# PCB-VU-SE-1.net
KiCad netlist of a schematic drawn in EAGLE
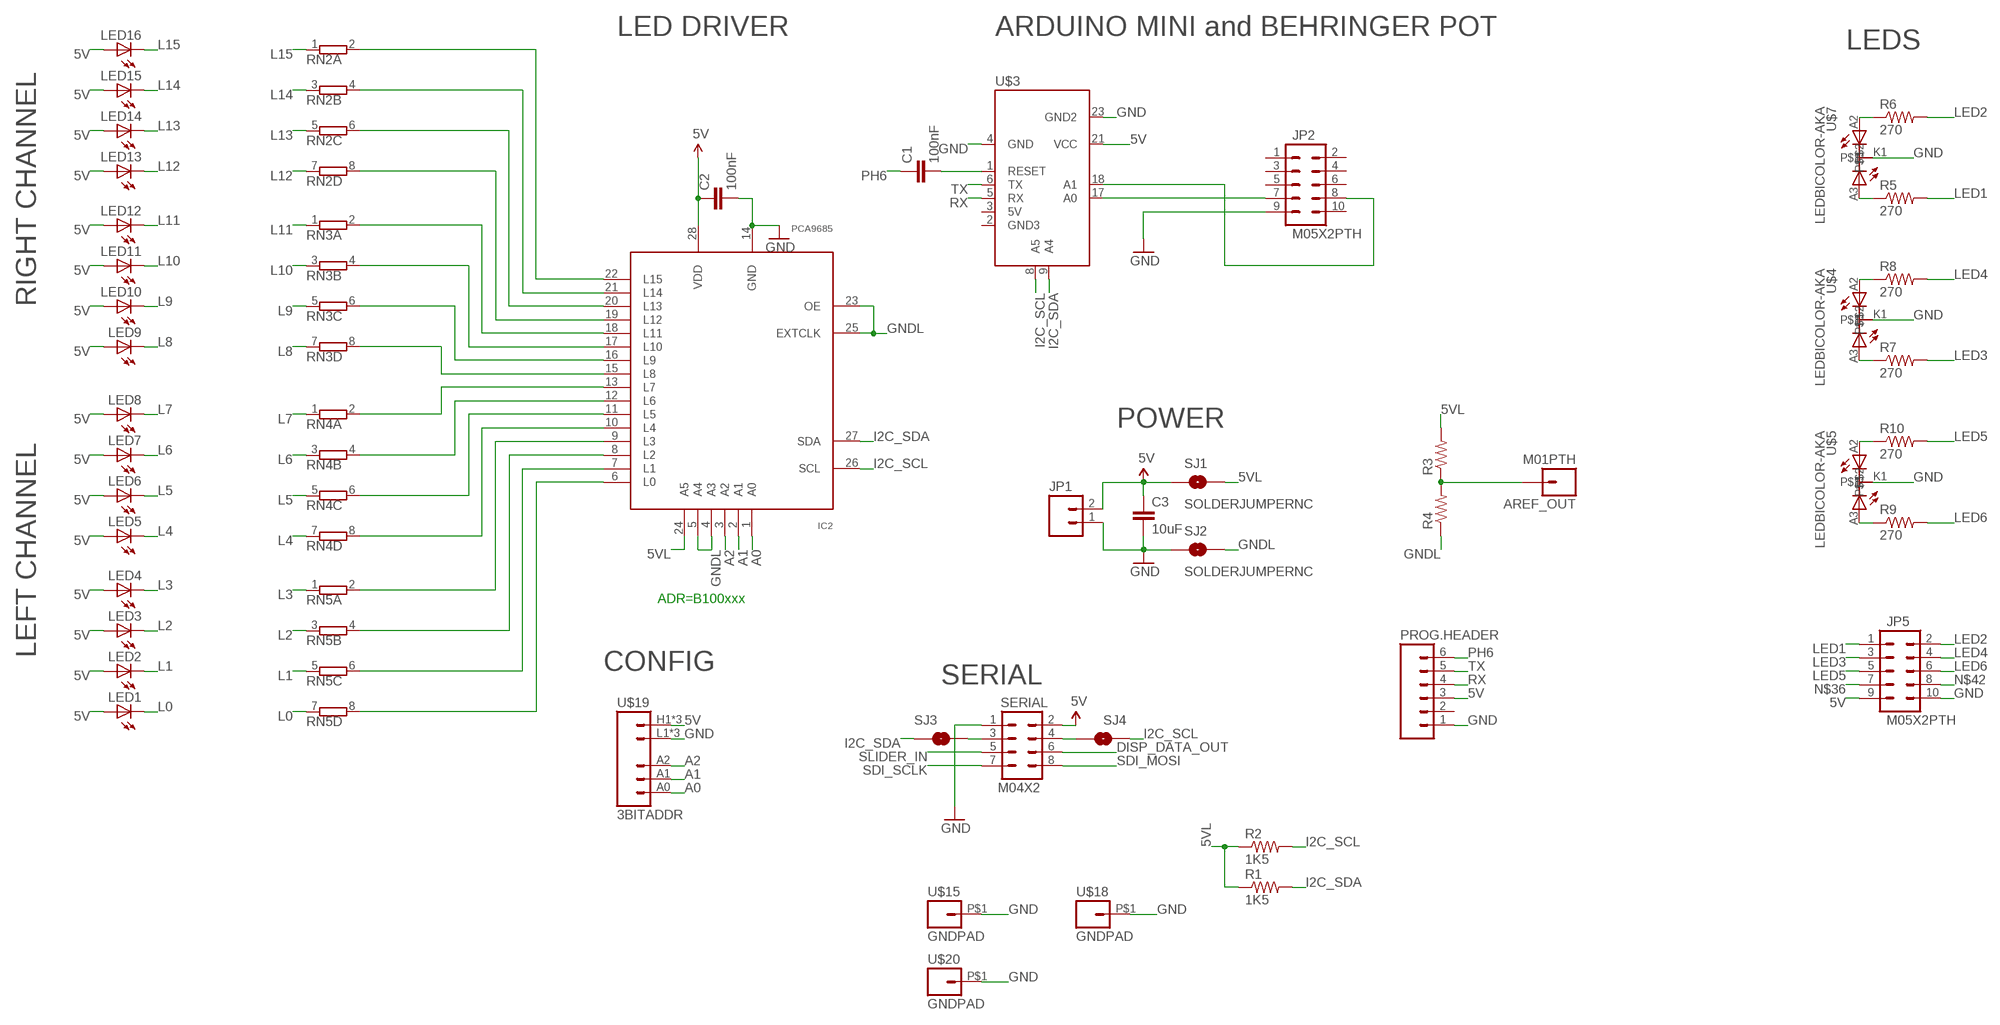
[diagram p0: schematic, sheet 1]

(export (version "E")
  (design (tool "Eeschema 10.0.6"))
  (components
    (comp (ref "AREF_OUT")
      (value "M01PTH")
      (footprint "eagle-import:1X01")
      (libsource (lib "eagle-import") (part "M01PTH"))
    )
    (comp (ref "C1")
      (value "100nF")
      (footprint "eagle-import:0603-CAP")
      (libsource (lib "eagle-import") (part "CAP0603-CAP"))
    )
    (comp (ref "C2")
      (value "100nF")
      (footprint "eagle-import:0603-CAP")
      (libsource (lib "eagle-import") (part "CAP0603-CAP"))
    )
    (comp (ref "C3")
      (value "10uF")
      (footprint "eagle-import:0805")
      (libsource (lib "eagle-import") (part "CAP0805"))
    )
    (comp (ref "IC2")
      (value "PCA9685")
      (footprint "eagle-import:TSSOP28")
      (libsource (lib "eagle-import") (part "PCA9685"))
    )
    (comp (ref "JP1")
      (value "M02PTH")
      (footprint "eagle-import:1X02")
      (libsource (lib "eagle-import") (part "M02PTH"))
    )
    (comp (ref "JP2")
      (value "M05X2PTH")
      (footprint "eagle-import:AVR_ICSP")
      (libsource (lib "eagle-import") (part "M05X2PTH"))
    )
    (comp (ref "JP5")
      (value "M05X2PTH")
      (footprint "eagle-import:AVR_ICSP")
      (libsource (lib "eagle-import") (part "M05X2PTH"))
    )
    (comp (ref "LED1")
      (value "LED3MM")
      (footprint "eagle-import:LED3MM")
      (libsource (lib "eagle-import") (part "LED3MM"))
    )
    (comp (ref "LED2")
      (value "LED3MM")
      (footprint "eagle-import:LED3MM")
      (libsource (lib "eagle-import") (part "LED3MM"))
    )
    (comp (ref "LED3")
      (value "LED3MM")
      (footprint "eagle-import:LED3MM")
      (libsource (lib "eagle-import") (part "LED3MM"))
    )
    (comp (ref "LED4")
      (value "LED3MM")
      (footprint "eagle-import:LED3MM")
      (libsource (lib "eagle-import") (part "LED3MM"))
    )
    (comp (ref "LED5")
      (value "LED3MM")
      (footprint "eagle-import:LED3MM")
      (libsource (lib "eagle-import") (part "LED3MM"))
    )
    (comp (ref "LED6")
      (value "LED3MM")
      (footprint "eagle-import:LED3MM")
      (libsource (lib "eagle-import") (part "LED3MM"))
    )
    (comp (ref "LED7")
      (value "LED3MM")
      (footprint "eagle-import:LED3MM")
      (libsource (lib "eagle-import") (part "LED3MM"))
    )
    (comp (ref "LED8")
      (value "LED3MM")
      (footprint "eagle-import:LED3MM")
      (libsource (lib "eagle-import") (part "LED3MM"))
    )
    (comp (ref "LED9")
      (value "LED3MM")
      (footprint "eagle-import:LED3MM")
      (libsource (lib "eagle-import") (part "LED3MM"))
    )
    (comp (ref "LED10")
      (value "LED3MM")
      (footprint "eagle-import:LED3MM")
      (libsource (lib "eagle-import") (part "LED3MM"))
    )
    (comp (ref "LED11")
      (value "LED3MM")
      (footprint "eagle-import:LED3MM")
      (libsource (lib "eagle-import") (part "LED3MM"))
    )
    (comp (ref "LED12")
      (value "LED3MM")
      (footprint "eagle-import:LED3MM")
      (libsource (lib "eagle-import") (part "LED3MM"))
    )
    (comp (ref "LED13")
      (value "LED3MM")
      (footprint "eagle-import:LED3MM")
      (libsource (lib "eagle-import") (part "LED3MM"))
    )
    (comp (ref "LED14")
      (value "LED3MM")
      (footprint "eagle-import:LED3MM")
      (libsource (lib "eagle-import") (part "LED3MM"))
    )
    (comp (ref "LED15")
      (value "LED3MM")
      (footprint "eagle-import:LED3MM")
      (libsource (lib "eagle-import") (part "LED3MM"))
    )
    (comp (ref "LED16")
      (value "LED3MM")
      (footprint "eagle-import:LED3MM")
      (libsource (lib "eagle-import") (part "LED3MM"))
    )
    (comp (ref "PROG.HEADER")
      (value "M06LOCK")
      (footprint "eagle-import:1X06_LOCK")
      (libsource (lib "eagle-import") (part "M06LOCK"))
    )
    (comp (ref "R1")
      (value "1K5")
      (footprint "eagle-import:0603-RES")
      (libsource (lib "eagle-import") (part "RESISTOR0603-RES"))
    )
    (comp (ref "R2")
      (value "1K5")
      (footprint "eagle-import:0603-RES")
      (libsource (lib "eagle-import") (part "RESISTOR0603-RES"))
    )
    (comp (ref "R3")
      (value "RESISTOR0603-RES")
      (footprint "eagle-import:0603-RES")
      (libsource (lib "eagle-import") (part "RESISTOR0603-RES"))
    )
    (comp (ref "R4")
      (value "RESISTOR0603-RES")
      (footprint "eagle-import:0603-RES")
      (libsource (lib "eagle-import") (part "RESISTOR0603-RES"))
    )
    (comp (ref "R5")
      (value "270")
      (footprint "eagle-import:0603-RES")
      (libsource (lib "eagle-import") (part "RESISTOR0603-RES"))
    )
    (comp (ref "R6")
      (value "270")
      (footprint "eagle-import:0603-RES")
      (libsource (lib "eagle-import") (part "RESISTOR0603-RES"))
    )
    (comp (ref "R7")
      (value "270")
      (footprint "eagle-import:0603-RES")
      (libsource (lib "eagle-import") (part "RESISTOR0603-RES"))
    )
    (comp (ref "R8")
      (value "270")
      (footprint "eagle-import:0603-RES")
      (libsource (lib "eagle-import") (part "RESISTOR0603-RES"))
    )
    (comp (ref "R9")
      (value "270")
      (footprint "eagle-import:0603-RES")
      (libsource (lib "eagle-import") (part "RESISTOR0603-RES"))
    )
    (comp (ref "R10")
      (value "270")
      (footprint "eagle-import:0603-RES")
      (libsource (lib "eagle-import") (part "RESISTOR0603-RES"))
    )
    (comp (ref "RN2")
      (value "E4R")
      (footprint "eagle-import:SIL8")
      (libsource (lib "eagle-import") (part "E4R"))
    )
    (comp (ref "RN3")
      (value "E4R")
      (footprint "eagle-import:SIL8")
      (libsource (lib "eagle-import") (part "E4R"))
    )
    (comp (ref "RN4")
      (value "E4R")
      (footprint "eagle-import:SIL8")
      (libsource (lib "eagle-import") (part "E4R"))
    )
    (comp (ref "RN5")
      (value "E4R")
      (footprint "eagle-import:SIL8")
      (libsource (lib "eagle-import") (part "E4R"))
    )
    (comp (ref "SERIAL")
      (value "M04X2")
      (footprint "eagle-import:2X4")
      (libsource (lib "eagle-import") (part "M04X2"))
    )
    (comp (ref "SJ1")
      (value "SOLDERJUMPERNC")
      (footprint "eagle-import:SJ_2S")
      (libsource (lib "eagle-import") (part "SOLDERJUMPERNC"))
    )
    (comp (ref "SJ2")
      (value "SOLDERJUMPERNC")
      (footprint "eagle-import:SJ_2S")
      (libsource (lib "eagle-import") (part "SOLDERJUMPERNC"))
    )
    (comp (ref "SJ3")
      (value "SOLDERJUMPERNC")
      (footprint "eagle-import:SJ_2S")
      (libsource (lib "eagle-import") (part "SOLDERJUMPERNC"))
    )
    (comp (ref "SJ4")
      (value "SOLDERJUMPERNC")
      (footprint "eagle-import:SJ_2S")
      (libsource (lib "eagle-import") (part "SOLDERJUMPERNC"))
    )
    (comp (ref "U$3")
      (value "ARDUINO_MINI_SE1")
      (footprint "eagle-import:ARDUINO_MINI_SE1")
      (libsource (lib "eagle-import") (part "ARDUINO_MINI_SE1"))
    )
    (comp (ref "U$4")
      (value "LEDBICOLOR-AKA")
      (footprint "eagle-import:LED5MM-BICOLOR")
      (libsource (lib "eagle-import") (part "LEDBICOLOR-AKA"))
    )
    (comp (ref "U$5")
      (value "LEDBICOLOR-AKA")
      (footprint "eagle-import:LED5MM-BICOLOR")
      (libsource (lib "eagle-import") (part "LEDBICOLOR-AKA"))
    )
    (comp (ref "U$7")
      (value "LEDBICOLOR-AKA")
      (footprint "eagle-import:LED5MM-BICOLOR")
      (libsource (lib "eagle-import") (part "LEDBICOLOR-AKA"))
    )
    (comp (ref "U$15")
      (value "GNDPAD")
      (footprint "eagle-import:3.2MMPAD")
      (libsource (lib "eagle-import") (part "GNDPAD"))
    )
    (comp (ref "U$18")
      (value "GNDPAD")
      (footprint "eagle-import:3.2MMPAD")
      (libsource (lib "eagle-import") (part "GNDPAD"))
    )
    (comp (ref "U$19")
      (value "3BITADDR")
      (footprint "eagle-import:3BITADDR")
      (libsource (lib "eagle-import") (part "3BITADDR"))
    )
    (comp (ref "U$20")
      (value "GNDPAD")
      (footprint "eagle-import:3.2MMPAD")
      (libsource (lib "eagle-import") (part "GNDPAD"))
    )
  )
  (nets
    (net (code "1") (name "/5VL") (class "Default")
      (node (ref "IC2") (pin "24") (pinfunction "A5_24") (pintype "input"))
      (node (ref "R1") (pin "1") (pinfunction "1_1") (pintype "passive"))
      (node (ref "R2") (pin "1") (pinfunction "1_1") (pintype "passive"))
      (node (ref "R3") (pin "2") (pinfunction "2_2") (pintype "passive"))
      (node (ref "SJ1") (pin "2") (pinfunction "2_2") (pintype "passive"))
    )
    (net (code "2") (name "/A0") (class "Default")
      (node (ref "IC2") (pin "1") (pinfunction "A0_1") (pintype "input"))
      (node (ref "U$19") (pin "A0") (pinfunction "A0_A0") (pintype "passive"))
    )
    (net (code "3") (name "/A1") (class "Default")
      (node (ref "IC2") (pin "2") (pinfunction "A1_2") (pintype "input"))
      (node (ref "U$19") (pin "A1") (pinfunction "A1_A1") (pintype "passive"))
    )
    (net (code "4") (name "/A2") (class "Default")
      (node (ref "IC2") (pin "3") (pinfunction "A2_3") (pintype "input"))
      (node (ref "U$19") (pin "A2") (pinfunction "A2_A2") (pintype "passive"))
    )
    (net (code "5") (name "/DISP_DATA_OUT") (class "Default")
      (node (ref "SERIAL") (pin "6") (pinfunction "6_6") (pintype "passive"))
    )
    (net (code "6") (name "/GNDL") (class "Default")
      (node (ref "IC2") (pin "23") (pinfunction "OE_23") (pintype "input"))
      (node (ref "IC2") (pin "25") (pinfunction "EXTCLK_25") (pintype "input"))
      (node (ref "IC2") (pin "4") (pinfunction "A3_4") (pintype "input"))
      (node (ref "IC2") (pin "5") (pinfunction "A4_5") (pintype "input"))
      (node (ref "R4") (pin "1") (pinfunction "1_1") (pintype "passive"))
      (node (ref "SJ2") (pin "2") (pinfunction "2_2") (pintype "passive"))
    )
    (net (code "7") (name "/I2C_SCL") (class "Default")
      (node (ref "IC2") (pin "26") (pinfunction "SCL_26") (pintype "input"))
      (node (ref "R2") (pin "2") (pinfunction "2_2") (pintype "passive"))
      (node (ref "SJ4") (pin "2") (pinfunction "2_2") (pintype "passive"))
      (node (ref "U$3") (pin "8") (pinfunction "A5_8") (pintype "bidirectional"))
    )
    (net (code "8") (name "/I2C_SDA") (class "Default")
      (node (ref "IC2") (pin "27") (pinfunction "SDA_27") (pintype "input"))
      (node (ref "R1") (pin "2") (pinfunction "2_2") (pintype "passive"))
      (node (ref "SJ3") (pin "1") (pinfunction "1_1") (pintype "passive"))
      (node (ref "U$3") (pin "9") (pinfunction "A4_9") (pintype "bidirectional"))
    )
    (net (code "9") (name "/L0") (class "Default")
      (node (ref "LED1") (pin "K") (pinfunction "C_K") (pintype "passive"))
      (node (ref "RN5") (pin "7") (pinfunction "1_7") (pintype "passive"))
    )
    (net (code "10") (name "/L1") (class "Default")
      (node (ref "LED2") (pin "K") (pinfunction "C_K") (pintype "passive"))
      (node (ref "RN5") (pin "5") (pinfunction "1_5") (pintype "passive"))
    )
    (net (code "11") (name "/L2") (class "Default")
      (node (ref "LED3") (pin "K") (pinfunction "C_K") (pintype "passive"))
      (node (ref "RN5") (pin "3") (pinfunction "1_3") (pintype "passive"))
    )
    (net (code "12") (name "/L3") (class "Default")
      (node (ref "LED4") (pin "K") (pinfunction "C_K") (pintype "passive"))
      (node (ref "RN5") (pin "1") (pinfunction "1_1") (pintype "passive"))
    )
    (net (code "13") (name "/L4") (class "Default")
      (node (ref "LED5") (pin "K") (pinfunction "C_K") (pintype "passive"))
      (node (ref "RN4") (pin "7") (pinfunction "1_7") (pintype "passive"))
    )
    (net (code "14") (name "/L5") (class "Default")
      (node (ref "LED6") (pin "K") (pinfunction "C_K") (pintype "passive"))
      (node (ref "RN4") (pin "5") (pinfunction "1_5") (pintype "passive"))
    )
    (net (code "15") (name "/L6") (class "Default")
      (node (ref "LED7") (pin "K") (pinfunction "C_K") (pintype "passive"))
      (node (ref "RN4") (pin "3") (pinfunction "1_3") (pintype "passive"))
    )
    (net (code "16") (name "/L7") (class "Default")
      (node (ref "LED8") (pin "K") (pinfunction "C_K") (pintype "passive"))
      (node (ref "RN4") (pin "1") (pinfunction "1_1") (pintype "passive"))
    )
    (net (code "17") (name "/L8") (class "Default")
      (node (ref "LED9") (pin "K") (pinfunction "C_K") (pintype "passive"))
      (node (ref "RN3") (pin "7") (pinfunction "1_7") (pintype "passive"))
    )
    (net (code "18") (name "/L9") (class "Default")
      (node (ref "LED10") (pin "K") (pinfunction "C_K") (pintype "passive"))
      (node (ref "RN3") (pin "5") (pinfunction "1_5") (pintype "passive"))
    )
    (net (code "19") (name "/L10") (class "Default")
      (node (ref "LED11") (pin "K") (pinfunction "C_K") (pintype "passive"))
      (node (ref "RN3") (pin "3") (pinfunction "1_3") (pintype "passive"))
    )
    (net (code "20") (name "/L11") (class "Default")
      (node (ref "LED12") (pin "K") (pinfunction "C_K") (pintype "passive"))
      (node (ref "RN3") (pin "1") (pinfunction "1_1") (pintype "passive"))
    )
    (net (code "21") (name "/L12") (class "Default")
      (node (ref "LED13") (pin "K") (pinfunction "C_K") (pintype "passive"))
      (node (ref "RN2") (pin "7") (pinfunction "1_7") (pintype "passive"))
    )
    (net (code "22") (name "/L13") (class "Default")
      (node (ref "LED14") (pin "K") (pinfunction "C_K") (pintype "passive"))
      (node (ref "RN2") (pin "5") (pinfunction "1_5") (pintype "passive"))
    )
    (net (code "23") (name "/L14") (class "Default")
      (node (ref "LED15") (pin "K") (pinfunction "C_K") (pintype "passive"))
      (node (ref "RN2") (pin "3") (pinfunction "1_3") (pintype "passive"))
    )
    (net (code "24") (name "/L15") (class "Default")
      (node (ref "LED16") (pin "K") (pinfunction "C_K") (pintype "passive"))
      (node (ref "RN2") (pin "1") (pinfunction "1_1") (pintype "passive"))
    )
    (net (code "25") (name "/LED1") (class "Default")
      (node (ref "JP5") (pin "1") (pinfunction "1_1") (pintype "passive"))
      (node (ref "R5") (pin "2") (pinfunction "2_2") (pintype "passive"))
    )
    (net (code "26") (name "/LED2") (class "Default")
      (node (ref "JP5") (pin "2") (pinfunction "2_2") (pintype "passive"))
      (node (ref "R6") (pin "2") (pinfunction "2_2") (pintype "passive"))
    )
    (net (code "27") (name "/LED3") (class "Default")
      (node (ref "JP5") (pin "3") (pinfunction "3_3") (pintype "passive"))
      (node (ref "R7") (pin "2") (pinfunction "2_2") (pintype "passive"))
    )
    (net (code "28") (name "/LED4") (class "Default")
      (node (ref "JP5") (pin "4") (pinfunction "4_4") (pintype "passive"))
      (node (ref "R8") (pin "2") (pinfunction "2_2") (pintype "passive"))
    )
    (net (code "29") (name "/LED5") (class "Default")
      (node (ref "JP5") (pin "5") (pinfunction "5_5") (pintype "passive"))
      (node (ref "R10") (pin "2") (pinfunction "2_2") (pintype "passive"))
    )
    (net (code "30") (name "/LED6") (class "Default")
      (node (ref "JP5") (pin "6") (pinfunction "6_6") (pintype "passive"))
      (node (ref "R9") (pin "2") (pinfunction "2_2") (pintype "passive"))
    )
    (net (code "31") (name "/N$36") (class "Default")
      (node (ref "JP5") (pin "7") (pinfunction "7_7") (pintype "passive"))
    )
    (net (code "32") (name "/N$42") (class "Default")
      (node (ref "JP5") (pin "8") (pinfunction "8_8") (pintype "passive"))
    )
    (net (code "33") (name "/PH6") (class "Default")
      (node (ref "C1") (pin "1") (pinfunction "1_1") (pintype "passive"))
      (node (ref "PROG.HEADER") (pin "6") (pinfunction "6_6") (pintype "passive"))
    )
    (net (code "34") (name "/RX") (class "Default")
      (node (ref "PROG.HEADER") (pin "4") (pinfunction "4_4") (pintype "passive"))
      (node (ref "U$3") (pin "5") (pinfunction "RX_5") (pintype "bidirectional"))
    )
    (net (code "35") (name "/SDI_MOSI") (class "Default")
      (node (ref "SERIAL") (pin "8") (pinfunction "8_8") (pintype "passive"))
    )
    (net (code "36") (name "/SDI_SCLK") (class "Default")
      (node (ref "SERIAL") (pin "7") (pinfunction "7_7") (pintype "passive"))
    )
    (net (code "37") (name "/SLIDER_IN") (class "Default")
      (node (ref "SERIAL") (pin "5") (pinfunction "5_5") (pintype "passive"))
    )
    (net (code "38") (name "/TX") (class "Default")
      (node (ref "PROG.HEADER") (pin "5") (pinfunction "5_5") (pintype "passive"))
      (node (ref "U$3") (pin "6") (pinfunction "TX_6") (pintype "bidirectional"))
    )
    (net (code "39") (name "5V") (class "Default")
      (node (ref "C2") (pin "1") (pinfunction "1_1") (pintype "passive"))
      (node (ref "C3") (pin "1") (pinfunction "1_1") (pintype "passive"))
      (node (ref "IC2") (pin "28") (pinfunction "VDD_28") (pintype "power_in"))
      (node (ref "JP1") (pin "2") (pinfunction "2_2") (pintype "passive"))
      (node (ref "JP5") (pin "9") (pinfunction "9_9") (pintype "passive"))
      (node (ref "LED1") (pin "A") (pinfunction "A_A") (pintype "passive"))
      (node (ref "LED10") (pin "A") (pinfunction "A_A") (pintype "passive"))
      (node (ref "LED11") (pin "A") (pinfunction "A_A") (pintype "passive"))
      (node (ref "LED12") (pin "A") (pinfunction "A_A") (pintype "passive"))
      (node (ref "LED13") (pin "A") (pinfunction "A_A") (pintype "passive"))
      (node (ref "LED14") (pin "A") (pinfunction "A_A") (pintype "passive"))
      (node (ref "LED15") (pin "A") (pinfunction "A_A") (pintype "passive"))
      (node (ref "LED16") (pin "A") (pinfunction "A_A") (pintype "passive"))
      (node (ref "LED2") (pin "A") (pinfunction "A_A") (pintype "passive"))
      (node (ref "LED3") (pin "A") (pinfunction "A_A") (pintype "passive"))
      (node (ref "LED4") (pin "A") (pinfunction "A_A") (pintype "passive"))
      (node (ref "LED5") (pin "A") (pinfunction "A_A") (pintype "passive"))
      (node (ref "LED6") (pin "A") (pinfunction "A_A") (pintype "passive"))
      (node (ref "LED7") (pin "A") (pinfunction "A_A") (pintype "passive"))
      (node (ref "LED8") (pin "A") (pinfunction "A_A") (pintype "passive"))
      (node (ref "LED9") (pin "A") (pinfunction "A_A") (pintype "passive"))
      (node (ref "PROG.HEADER") (pin "3") (pinfunction "3_3") (pintype "passive"))
      (node (ref "SERIAL") (pin "2") (pinfunction "2_2") (pintype "passive"))
      (node (ref "SJ1") (pin "1") (pinfunction "1_1") (pintype "passive"))
      (node (ref "U$19") (pin "H1") (pinfunction "VCC_H1") (pintype "passive"))
      (node (ref "U$19") (pin "H2") (pinfunction "VCC_H2") (pintype "passive"))
      (node (ref "U$19") (pin "H3") (pinfunction "VCC_H3") (pintype "passive"))
      (node (ref "U$3") (pin "21") (pinfunction "VCC_21") (pintype "bidirectional"))
    )
    (net (code "40") (name "GND") (class "Default")
      (node (ref "C2") (pin "2") (pinfunction "2_2") (pintype "passive"))
      (node (ref "C3") (pin "2") (pinfunction "2_2") (pintype "passive"))
      (node (ref "IC2") (pin "14") (pinfunction "GND_14") (pintype "power_in"))
      (node (ref "JP1") (pin "1") (pinfunction "1_1") (pintype "passive"))
      (node (ref "JP2") (pin "9") (pinfunction "9_9") (pintype "passive"))
      (node (ref "JP5") (pin "10") (pinfunction "10_10") (pintype "passive"))
      (node (ref "PROG.HEADER") (pin "1") (pinfunction "1_1") (pintype "passive"))
      (node (ref "SERIAL") (pin "1") (pinfunction "1_1") (pintype "passive"))
      (node (ref "SJ2") (pin "1") (pinfunction "1_1") (pintype "passive"))
      (node (ref "U$15") (pin "P$1") (pinfunction "1_P$1") (pintype "passive"))
      (node (ref "U$18") (pin "P$1") (pinfunction "1_P$1") (pintype "passive"))
      (node (ref "U$19") (pin "L1") (pinfunction "GND_L1") (pintype "passive"))
      (node (ref "U$19") (pin "L2") (pinfunction "GND_L2") (pintype "passive"))
      (node (ref "U$19") (pin "L3") (pinfunction "GND_L3") (pintype "passive"))
      (node (ref "U$20") (pin "P$1") (pinfunction "1_P$1") (pintype "passive"))
      (node (ref "U$3") (pin "23") (pinfunction "GND2_23") (pintype "bidirectional"))
      (node (ref "U$3") (pin "4") (pinfunction "GND_4") (pintype "bidirectional"))
      (node (ref "U$4") (pin "K1") (pinfunction "P$1_K1") (pintype "bidirectional"))
      (node (ref "U$5") (pin "K1") (pinfunction "P$1_K1") (pintype "bidirectional"))
      (node (ref "U$7") (pin "K1") (pinfunction "P$1_K1") (pintype "bidirectional"))
    )
    (net (code "41") (name "Net-(AREF_OUT-Pad1)") (class "Default")
      (node (ref "AREF_OUT") (pin "1") (pinfunction "1_1") (pintype "passive"))
      (node (ref "R3") (pin "1") (pinfunction "1_1") (pintype "passive"))
      (node (ref "R4") (pin "2") (pinfunction "2_2") (pintype "passive"))
    )
    (net (code "42") (name "Net-(IC2-L0)") (class "Default")
      (node (ref "IC2") (pin "6") (pinfunction "L0_6") (pintype "output"))
      (node (ref "RN5") (pin "8") (pinfunction "2_8") (pintype "passive"))
    )
    (net (code "43") (name "Net-(IC2-L1)") (class "Default")
      (node (ref "IC2") (pin "7") (pinfunction "L1_7") (pintype "output"))
      (node (ref "RN5") (pin "6") (pinfunction "2_6") (pintype "passive"))
    )
    (net (code "44") (name "Net-(IC2-L2)") (class "Default")
      (node (ref "IC2") (pin "8") (pinfunction "L2_8") (pintype "output"))
      (node (ref "RN5") (pin "4") (pinfunction "2_4") (pintype "passive"))
    )
    (net (code "45") (name "Net-(IC2-L3)") (class "Default")
      (node (ref "IC2") (pin "9") (pinfunction "L3_9") (pintype "output"))
      (node (ref "RN5") (pin "2") (pinfunction "2_2") (pintype "passive"))
    )
    (net (code "46") (name "Net-(IC2-L4)") (class "Default")
      (node (ref "IC2") (pin "10") (pinfunction "L4_10") (pintype "output"))
      (node (ref "RN4") (pin "8") (pinfunction "2_8") (pintype "passive"))
    )
    (net (code "47") (name "Net-(IC2-L5)") (class "Default")
      (node (ref "IC2") (pin "11") (pinfunction "L5_11") (pintype "output"))
      (node (ref "RN4") (pin "6") (pinfunction "2_6") (pintype "passive"))
    )
    (net (code "48") (name "Net-(IC2-L6)") (class "Default")
      (node (ref "IC2") (pin "12") (pinfunction "L6_12") (pintype "output"))
      (node (ref "RN4") (pin "4") (pinfunction "2_4") (pintype "passive"))
    )
    (net (code "49") (name "Net-(IC2-L7)") (class "Default")
      (node (ref "IC2") (pin "13") (pinfunction "L7_13") (pintype "output"))
      (node (ref "RN4") (pin "2") (pinfunction "2_2") (pintype "passive"))
    )
    (net (code "50") (name "Net-(IC2-L8)") (class "Default")
      (node (ref "IC2") (pin "15") (pinfunction "L8_15") (pintype "output"))
      (node (ref "RN3") (pin "8") (pinfunction "2_8") (pintype "passive"))
    )
    (net (code "51") (name "Net-(IC2-L9)") (class "Default")
      (node (ref "IC2") (pin "16") (pinfunction "L9_16") (pintype "output"))
      (node (ref "RN3") (pin "6") (pinfunction "2_6") (pintype "passive"))
    )
    (net (code "52") (name "Net-(IC2-L10)") (class "Default")
      (node (ref "IC2") (pin "17") (pinfunction "L10_17") (pintype "output"))
      (node (ref "RN3") (pin "4") (pinfunction "2_4") (pintype "passive"))
    )
    (net (code "53") (name "Net-(IC2-L11)") (class "Default")
      (node (ref "IC2") (pin "18") (pinfunction "L11_18") (pintype "output"))
      (node (ref "RN3") (pin "2") (pinfunction "2_2") (pintype "passive"))
    )
    (net (code "54") (name "Net-(IC2-L12)") (class "Default")
      (node (ref "IC2") (pin "19") (pinfunction "L12_19") (pintype "output"))
      (node (ref "RN2") (pin "8") (pinfunction "2_8") (pintype "passive"))
    )
    (net (code "55") (name "Net-(IC2-L13)") (class "Default")
      (node (ref "IC2") (pin "20") (pinfunction "L13_20") (pintype "output"))
      (node (ref "RN2") (pin "6") (pinfunction "2_6") (pintype "passive"))
    )
    (net (code "56") (name "Net-(IC2-L14)") (class "Default")
      (node (ref "IC2") (pin "21") (pinfunction "L14_21") (pintype "output"))
      (node (ref "RN2") (pin "4") (pinfunction "2_4") (pintype "passive"))
    )
    (net (code "57") (name "Net-(IC2-L15)") (class "Default")
      (node (ref "IC2") (pin "22") (pinfunction "L15_22") (pintype "output"))
      (node (ref "RN2") (pin "2") (pinfunction "2_2") (pintype "passive"))
    )
    (net (code "58") (name "Net-(SERIAL-Pad3)") (class "Default")
      (node (ref "SERIAL") (pin "3") (pinfunction "3_3") (pintype "passive"))
      (node (ref "SJ3") (pin "2") (pinfunction "2_2") (pintype "passive"))
    )
    (net (code "59") (name "Net-(SERIAL-Pad4)") (class "Default")
      (node (ref "SERIAL") (pin "4") (pinfunction "4_4") (pintype "passive"))
      (node (ref "SJ4") (pin "1") (pinfunction "1_1") (pintype "passive"))
    )
    (net (code "60") (name "Net-(U$3-A0)") (class "Default")
      (node (ref "JP2") (pin "7") (pinfunction "7_7") (pintype "passive"))
      (node (ref "U$3") (pin "17") (pinfunction "A0_17") (pintype "bidirectional"))
    )
    (net (code "61") (name "Net-(U$3-A1)") (class "Default")
      (node (ref "JP2") (pin "8") (pinfunction "8_8") (pintype "passive"))
      (node (ref "U$3") (pin "18") (pinfunction "A1_18") (pintype "bidirectional"))
    )
    (net (code "62") (name "Net-(U$3-RESET)") (class "Default")
      (node (ref "C1") (pin "2") (pinfunction "2_2") (pintype "passive"))
      (node (ref "U$3") (pin "1") (pinfunction "RESET_1") (pintype "bidirectional"))
    )
    (net (code "63") (name "Net-(U$4-P$2)") (class "Default")
      (node (ref "R8") (pin "1") (pinfunction "1_1") (pintype "passive"))
      (node (ref "U$4") (pin "A2") (pinfunction "P$2_A2") (pintype "bidirectional"))
    )
    (net (code "64") (name "Net-(U$4-P$3)") (class "Default")
      (node (ref "R7") (pin "1") (pinfunction "1_1") (pintype "passive"))
      (node (ref "U$4") (pin "A3") (pinfunction "P$3_A3") (pintype "bidirectional"))
    )
    (net (code "65") (name "Net-(U$5-P$2)") (class "Default")
      (node (ref "R10") (pin "1") (pinfunction "1_1") (pintype "passive"))
      (node (ref "U$5") (pin "A2") (pinfunction "P$2_A2") (pintype "bidirectional"))
    )
    (net (code "66") (name "Net-(U$5-P$3)") (class "Default")
      (node (ref "R9") (pin "1") (pinfunction "1_1") (pintype "passive"))
      (node (ref "U$5") (pin "A3") (pinfunction "P$3_A3") (pintype "bidirectional"))
    )
    (net (code "67") (name "Net-(U$7-P$2)") (class "Default")
      (node (ref "R6") (pin "1") (pinfunction "1_1") (pintype "passive"))
      (node (ref "U$7") (pin "A2") (pinfunction "P$2_A2") (pintype "bidirectional"))
    )
    (net (code "68") (name "Net-(U$7-P$3)") (class "Default")
      (node (ref "R5") (pin "1") (pinfunction "1_1") (pintype "passive"))
      (node (ref "U$7") (pin "A3") (pinfunction "P$3_A3") (pintype "bidirectional"))
    )
    (net (code "69") (name "unconnected-(JP2-Pad1)") (class "Default")
      (node (ref "JP2") (pin "1") (pinfunction "1_1") (pintype "passive"))
    )
    (net (code "70") (name "unconnected-(JP2-Pad2)") (class "Default")
      (node (ref "JP2") (pin "2") (pinfunction "2_2") (pintype "passive"))
    )
    (net (code "71") (name "unconnected-(JP2-Pad3)") (class "Default")
      (node (ref "JP2") (pin "3") (pinfunction "3_3") (pintype "passive"))
    )
    (net (code "72") (name "unconnected-(JP2-Pad4)") (class "Default")
      (node (ref "JP2") (pin "4") (pinfunction "4_4") (pintype "passive"))
    )
    (net (code "73") (name "unconnected-(JP2-Pad5)") (class "Default")
      (node (ref "JP2") (pin "5") (pinfunction "5_5") (pintype "passive"))
    )
    (net (code "74") (name "unconnected-(JP2-Pad6)") (class "Default")
      (node (ref "JP2") (pin "6") (pinfunction "6_6") (pintype "passive"))
    )
    (net (code "75") (name "unconnected-(JP2-Pad10)") (class "Default")
      (node (ref "JP2") (pin "10") (pinfunction "10_10") (pintype "passive"))
    )
    (net (code "76") (name "unconnected-(PROG.HEADER-Pad2)") (class "Default")
      (node (ref "PROG.HEADER") (pin "2") (pinfunction "2_2") (pintype "passive"))
    )
    (net (code "77") (name "unconnected-(U$3-5V-Pad3)") (class "Default")
      (node (ref "U$3") (pin "3") (pinfunction "5V_3") (pintype "bidirectional"))
    )
    (net (code "78") (name "unconnected-(U$3-GND3-Pad2)") (class "Default")
      (node (ref "U$3") (pin "2") (pinfunction "GND3_2") (pintype "bidirectional"))
    )
  )
)
